# esp8266_rgb_controller_v2.net
KiCad netlist of a schematic drawn in EAGLE
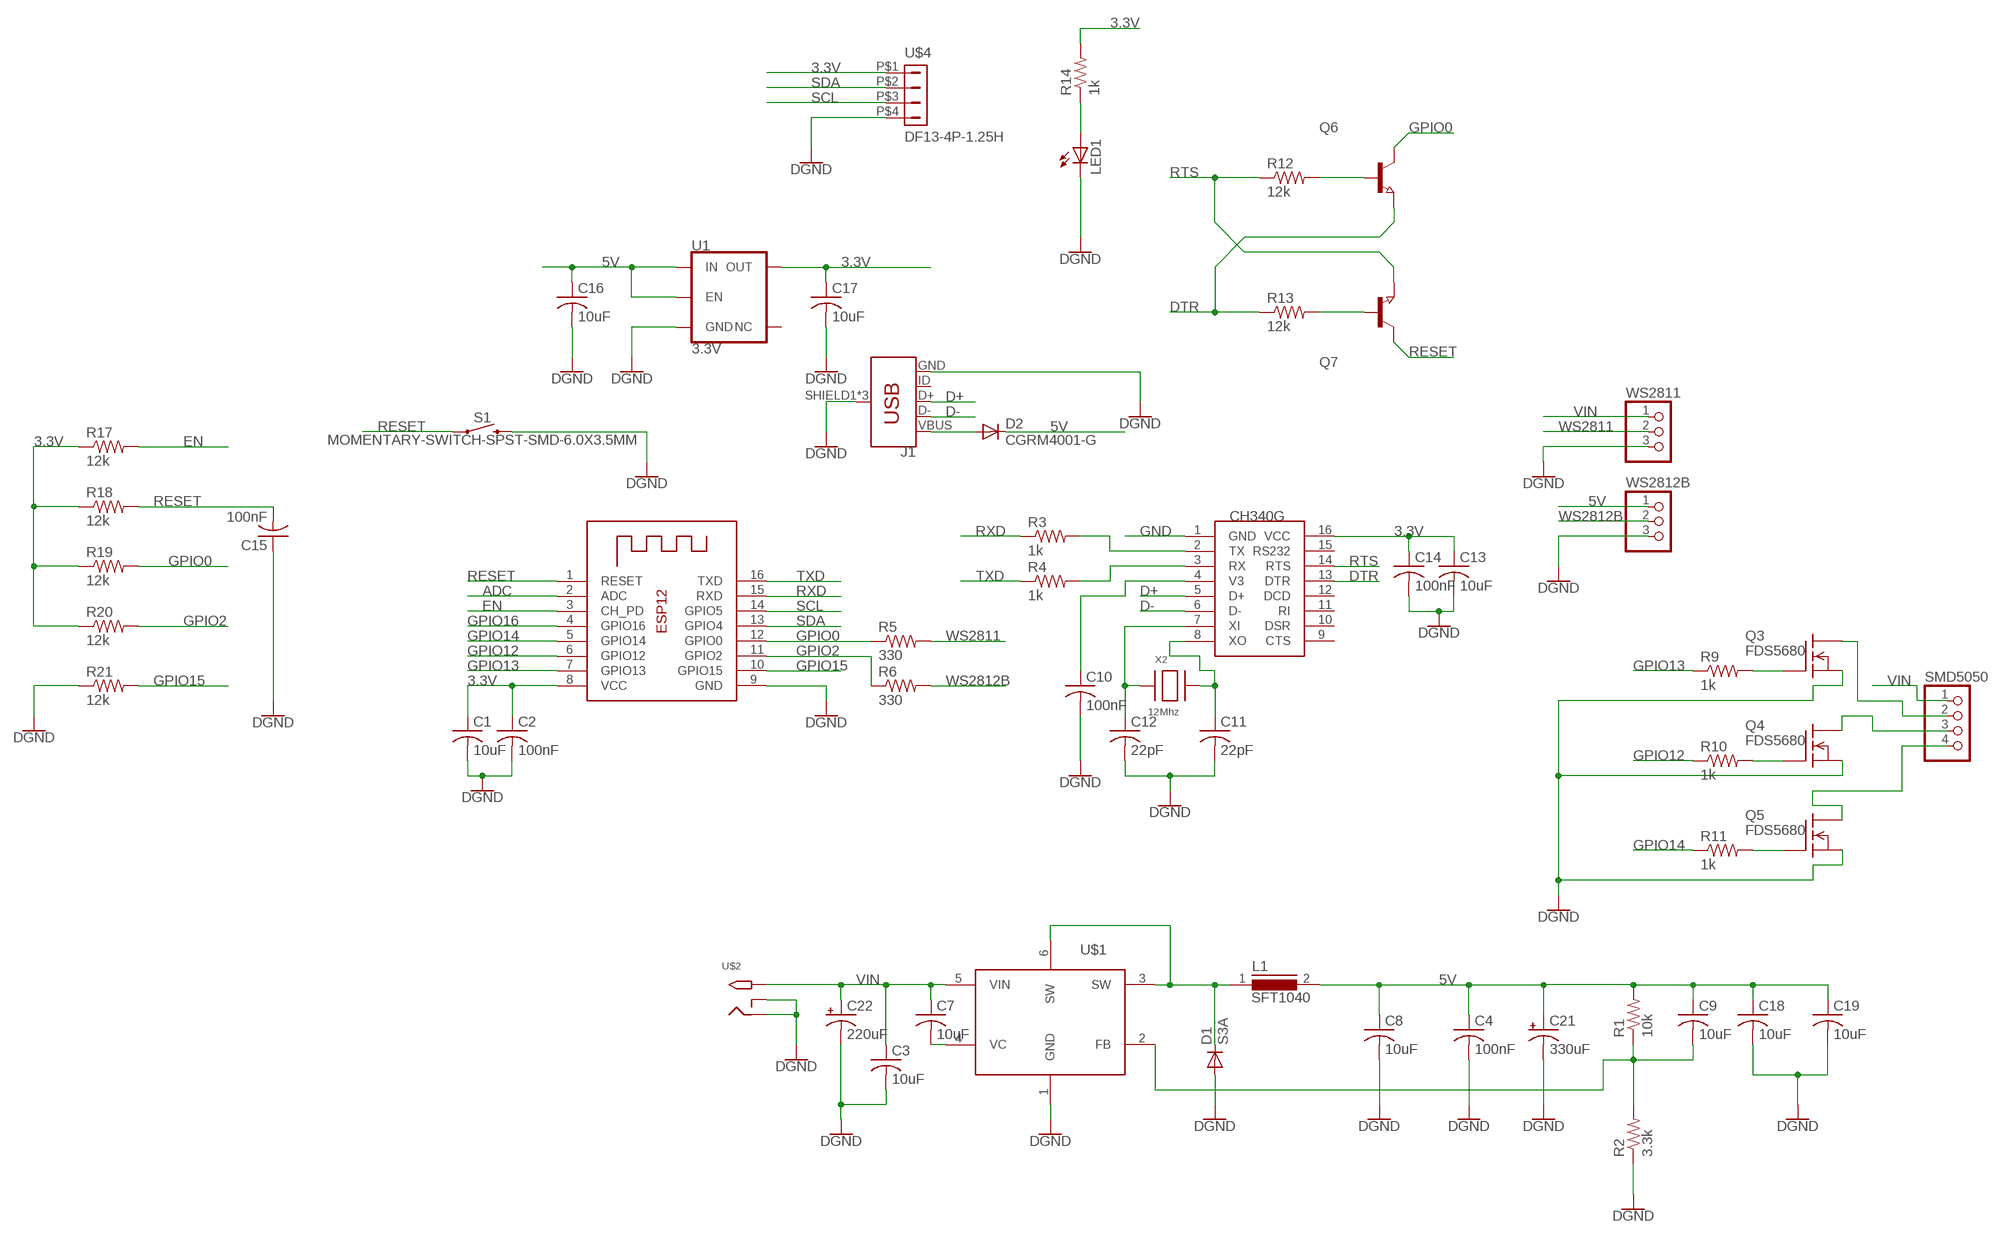
[diagram p0: schematic, sheet 1]

(export (version "E")
  (design (tool "Eeschema 10.0.6"))
  (components
    (comp (ref "C1")
      (value "10uF")
      (footprint "eagle-import:C0805")
      (libsource (lib "eagle-import") (part "C-USC0805"))
    )
    (comp (ref "C2")
      (value "100nF")
      (footprint "eagle-import:C0805")
      (libsource (lib "eagle-import") (part "C-USC0805"))
    )
    (comp (ref "C3")
      (value "10uF")
      (footprint "eagle-import:C0805")
      (libsource (lib "eagle-import") (part "C-USC0805"))
    )
    (comp (ref "C4")
      (value "100nF")
      (footprint "eagle-import:C0805")
      (libsource (lib "eagle-import") (part "C-USC0805"))
    )
    (comp (ref "C7")
      (value "10uF")
      (footprint "eagle-import:C0805")
      (libsource (lib "eagle-import") (part "C-USC0805"))
    )
    (comp (ref "C8")
      (value "10uF")
      (footprint "eagle-import:C0805")
      (libsource (lib "eagle-import") (part "C-USC0805"))
    )
    (comp (ref "C9")
      (value "10uF")
      (footprint "eagle-import:C0805")
      (libsource (lib "eagle-import") (part "C-USC0805"))
    )
    (comp (ref "C10")
      (value "100nF")
      (footprint "eagle-import:C0805")
      (libsource (lib "eagle-import") (part "C-USC0805"))
    )
    (comp (ref "C11")
      (value "22pF")
      (footprint "eagle-import:C0805")
      (libsource (lib "eagle-import") (part "C-USC0805"))
    )
    (comp (ref "C12")
      (value "22pF")
      (footprint "eagle-import:C0805")
      (libsource (lib "eagle-import") (part "C-USC0805"))
    )
    (comp (ref "C13")
      (value "10uF")
      (footprint "eagle-import:C0805")
      (libsource (lib "eagle-import") (part "C-USC0805"))
    )
    (comp (ref "C14")
      (value "100nF")
      (footprint "eagle-import:C0805")
      (libsource (lib "eagle-import") (part "C-USC0805"))
    )
    (comp (ref "C15")
      (value "100nF")
      (footprint "eagle-import:C0805")
      (libsource (lib "eagle-import") (part "C-USC0805"))
    )
    (comp (ref "C16")
      (value "10uF")
      (footprint "eagle-import:C1210")
      (libsource (lib "eagle-import") (part "C-USC1210"))
    )
    (comp (ref "C17")
      (value "10uF")
      (footprint "eagle-import:C0805")
      (libsource (lib "eagle-import") (part "C-USC0805"))
    )
    (comp (ref "C18")
      (value "10uF")
      (footprint "eagle-import:C0805")
      (libsource (lib "eagle-import") (part "C-USC0805"))
    )
    (comp (ref "C19")
      (value "10uF")
      (footprint "eagle-import:C0805")
      (libsource (lib "eagle-import") (part "C-USC0805"))
    )
    (comp (ref "C21")
      (value "330uF")
      (footprint "eagle-import:153CLV-0810")
      (libsource (lib "eagle-import") (part "CPOL-US153CLV-0810"))
    )
    (comp (ref "C22")
      (value "220uF")
      (footprint "eagle-import:153CLV-0810")
      (libsource (lib "eagle-import") (part "CPOL-US153CLV-0810"))
    )
    (comp (ref "D1")
      (value "S3A")
      (footprint "eagle-import:DO214AB")
      (fields (field (name "MF") "Fairchild"))
      (libsource (lib "eagle-import") (part "S3A"))
    )
    (comp (ref "D2")
      (value "CGRM4001-G")
      (footprint "eagle-import:SOD-123_MINI-SMA")
      (libsource (lib "eagle-import") (part "CGRM400-G1"))
    )
    (comp (ref "J1")
      (value "USB_MICRO-BREDUCED_PASTE")
      (footprint "eagle-import:USB-B-MICRO-SMD_RED_PASTE")
      (libsource (lib "eagle-import") (part "USB_MICRO-BREDUCED_PASTE"))
    )
    (comp (ref "L1")
      (value "SFT1040")
      (footprint "eagle-import:SFT1040")
      (libsource (lib "eagle-import") (part "SFT1040"))
    )
    (comp (ref "LED1")
      (value "LEDCHIP-LED0603")
      (footprint "eagle-import:CHIP-LED0603")
      (libsource (lib "eagle-import") (part "LEDCHIP-LED0603"))
    )
    (comp (ref "Q3")
      (value "FDS5680")
      (footprint "eagle-import:SO-8")
      (libsource (lib "eagle-import") (part "FDS5680"))
    )
    (comp (ref "Q4")
      (value "FDS5680")
      (footprint "eagle-import:SO-8")
      (libsource (lib "eagle-import") (part "FDS5680"))
    )
    (comp (ref "Q5")
      (value "FDS5680")
      (footprint "eagle-import:SO-8")
      (libsource (lib "eagle-import") (part "FDS5680"))
    )
    (comp (ref "Q6")
      (value "NPN-TRANSISTOR_SOT23")
      (footprint "eagle-import:SOT23")
      (libsource (lib "eagle-import") (part "NPN-TRANSISTOR_SOT23"))
    )
    (comp (ref "Q7")
      (value "NPN-TRANSISTOR_SOT23")
      (footprint "eagle-import:SOT23")
      (libsource (lib "eagle-import") (part "NPN-TRANSISTOR_SOT23"))
    )
    (comp (ref "R1")
      (value "10k")
      (footprint "eagle-import:R0805")
      (libsource (lib "eagle-import") (part "R-US_R0805"))
    )
    (comp (ref "R2")
      (value "3.3k")
      (footprint "eagle-import:R0805")
      (libsource (lib "eagle-import") (part "R-US_R0805"))
    )
    (comp (ref "R3")
      (value "1k")
      (footprint "eagle-import:R0805")
      (libsource (lib "eagle-import") (part "R-US_R0805"))
    )
    (comp (ref "R4")
      (value "1k")
      (footprint "eagle-import:R0805")
      (libsource (lib "eagle-import") (part "R-US_R0805"))
    )
    (comp (ref "R5")
      (value "330")
      (footprint "eagle-import:R0805")
      (libsource (lib "eagle-import") (part "R-US_R0805"))
    )
    (comp (ref "R6")
      (value "330")
      (footprint "eagle-import:R0805")
      (libsource (lib "eagle-import") (part "R-US_R0805"))
    )
    (comp (ref "R9")
      (value "1k")
      (footprint "eagle-import:R0805")
      (libsource (lib "eagle-import") (part "R-US_R0805"))
    )
    (comp (ref "R10")
      (value "1k")
      (footprint "eagle-import:R0805")
      (libsource (lib "eagle-import") (part "R-US_R0805"))
    )
    (comp (ref "R11")
      (value "1k")
      (footprint "eagle-import:R0805")
      (libsource (lib "eagle-import") (part "R-US_R0805"))
    )
    (comp (ref "R12")
      (value "12k")
      (footprint "eagle-import:R0805")
      (libsource (lib "eagle-import") (part "R-US_R0805"))
    )
    (comp (ref "R13")
      (value "12k")
      (footprint "eagle-import:R0805")
      (libsource (lib "eagle-import") (part "R-US_R0805"))
    )
    (comp (ref "R14")
      (value "1k")
      (footprint "eagle-import:R0805")
      (libsource (lib "eagle-import") (part "R-US_R0805"))
    )
    (comp (ref "R17")
      (value "12k")
      (footprint "eagle-import:R0805")
      (libsource (lib "eagle-import") (part "R-US_R0805"))
    )
    (comp (ref "R18")
      (value "12k")
      (footprint "eagle-import:R0805")
      (libsource (lib "eagle-import") (part "R-US_R0805"))
    )
    (comp (ref "R19")
      (value "12k")
      (footprint "eagle-import:R0805")
      (libsource (lib "eagle-import") (part "R-US_R0805"))
    )
    (comp (ref "R20")
      (value "12k")
      (footprint "eagle-import:R0805")
      (libsource (lib "eagle-import") (part "R-US_R0805"))
    )
    (comp (ref "R21")
      (value "12k")
      (footprint "eagle-import:R0805")
      (libsource (lib "eagle-import") (part "R-US_R0805"))
    )
    (comp (ref "S1")
      (value "MOMENTARY-SWITCH-SPST-SMD-6.0X3.5MM")
      (footprint "eagle-import:TACTILE_SWITCH_SMD_6.0X3.5MM")
      (libsource (lib "eagle-import") (part "MOMENTARY-SWITCH-SPST-SMD-6.0X3.5MM"))
    )
    (comp (ref "SMD5050")
      (value "PINHD-1X4")
      (footprint "eagle-import:1X04")
      (libsource (lib "eagle-import") (part "PINHD-1X4"))
    )
    (comp (ref "U$1")
      (value "XL4015")
      (footprint "eagle-import:TO263-5")
      (libsource (lib "eagle-import") (part "XL4015"))
    )
    (comp (ref "U$2")
      (value "2.1MMJACKTHM")
      (footprint "eagle-import:PJ-102A")
      (libsource (lib "eagle-import") (part "2.1MMJACKTHM"))
    )
    (comp (ref "U$3")
      (value "CH340G")
      (footprint "eagle-import:SOIC16")
      (libsource (lib "eagle-import") (part "CH340G"))
    )
    (comp (ref "U$4")
      (value "DF13-4P-1.25H")
      (footprint "eagle-import:DF13A-4P-1.25H")
      (libsource (lib "eagle-import") (part "DF13-4P-1.25H"))
    )
    (comp (ref "U1")
      (value "3.3V")
      (footprint "eagle-import:SOT23-5")
      (libsource (lib "eagle-import") (part "V_REG_AP2112K-3.3V"))
    )
    (comp (ref "WS2811")
      (value "PINHD-1X3")
      (footprint "eagle-import:1X03")
      (libsource (lib "eagle-import") (part "PINHD-1X3"))
    )
    (comp (ref "WS2812B")
      (value "PINHD-1X3")
      (footprint "eagle-import:1X03")
      (libsource (lib "eagle-import") (part "PINHD-1X3"))
    )
    (comp (ref "X1")
      (value "ESP-12F")
      (footprint "eagle-import:ESP-12")
      (libsource (lib "eagle-import") (part "ESP-12F"))
    )
    (comp (ref "X2")
      (value "12Mhz")
      (footprint "eagle-import:NX5032")
      (libsource (lib "eagle-import") (part "XTALNX5032"))
    )
  )
  (nets
    (net (code "1") (name "/3.3V") (class "Default")
      (node (ref "C1") (pin "1") (pinfunction "1_1") (pintype "passive"))
      (node (ref "C13") (pin "1") (pinfunction "1_1") (pintype "passive"))
      (node (ref "C14") (pin "1") (pinfunction "1_1") (pintype "passive"))
      (node (ref "C17") (pin "1") (pinfunction "1_1") (pintype "passive"))
      (node (ref "C2") (pin "1") (pinfunction "1_1") (pintype "passive"))
      (node (ref "R14") (pin "2") (pinfunction "2_2") (pintype "passive"))
      (node (ref "R17") (pin "1") (pinfunction "1_1") (pintype "passive"))
      (node (ref "R18") (pin "1") (pinfunction "1_1") (pintype "passive"))
      (node (ref "R19") (pin "1") (pinfunction "1_1") (pintype "passive"))
      (node (ref "R20") (pin "1") (pinfunction "1_1") (pintype "passive"))
      (node (ref "U$3") (pin "16") (pinfunction "VCC_16") (pintype "bidirectional"))
      (node (ref "U$4") (pin "P$1") (pinfunction "1_P$1") (pintype "passive"))
      (node (ref "U1") (pin "5") (pinfunction "OUT_5") (pintype "passive"))
      (node (ref "X1") (pin "8") (pinfunction "VCC_8") (pintype "power_in"))
    )
    (net (code "2") (name "/5V") (class "Default")
      (node (ref "C16") (pin "1") (pinfunction "1_1") (pintype "passive"))
      (node (ref "C18") (pin "1") (pinfunction "1_1") (pintype "passive"))
      (node (ref "C19") (pin "1") (pinfunction "1_1") (pintype "passive"))
      (node (ref "C21") (pin "+") (pinfunction "+_+") (pintype "passive"))
      (node (ref "C4") (pin "1") (pinfunction "1_1") (pintype "passive"))
      (node (ref "C8") (pin "1") (pinfunction "1_1") (pintype "passive"))
      (node (ref "C9") (pin "1") (pinfunction "1_1") (pintype "passive"))
      (node (ref "D2") (pin "C") (pinfunction "C_C") (pintype "passive"))
      (node (ref "L1") (pin "2") (pinfunction "2_2") (pintype "passive"))
      (node (ref "R1") (pin "2") (pinfunction "2_2") (pintype "passive"))
      (node (ref "U1") (pin "1") (pinfunction "IN_1") (pintype "input"))
      (node (ref "U1") (pin "3") (pinfunction "EN_3") (pintype "input"))
      (node (ref "WS2812B") (pin "1") (pinfunction "1_1") (pintype "passive"))
    )
    (net (code "3") (name "/ADC") (class "Default")
      (node (ref "X1") (pin "2") (pinfunction "ADC_2") (pintype "passive"))
    )
    (net (code "4") (name "/D+") (class "Default")
      (node (ref "J1") (pin "D+") (pinfunction "D+_D+") (pintype "bidirectional"))
      (node (ref "U$3") (pin "5") (pinfunction "D+_5") (pintype "bidirectional"))
    )
    (net (code "5") (name "/D-") (class "Default")
      (node (ref "J1") (pin "D-") (pinfunction "D-_D-") (pintype "bidirectional"))
      (node (ref "U$3") (pin "6") (pinfunction "D-_6") (pintype "bidirectional"))
    )
    (net (code "6") (name "/DTR") (class "Default")
      (node (ref "Q6") (pin "2") (pinfunction "E_2") (pintype "passive"))
      (node (ref "R13") (pin "1") (pinfunction "1_1") (pintype "passive"))
      (node (ref "U$3") (pin "13") (pinfunction "DTR_13") (pintype "bidirectional"))
    )
    (net (code "7") (name "/EN") (class "Default")
      (node (ref "R17") (pin "2") (pinfunction "2_2") (pintype "passive"))
      (node (ref "X1") (pin "3") (pinfunction "CH_PD_3") (pintype "input"))
    )
    (net (code "8") (name "/GPIO0") (class "Default")
      (node (ref "Q6") (pin "3") (pinfunction "C_3") (pintype "passive"))
      (node (ref "R19") (pin "2") (pinfunction "2_2") (pintype "passive"))
      (node (ref "R5") (pin "1") (pinfunction "1_1") (pintype "passive"))
      (node (ref "X1") (pin "12") (pinfunction "GPIO0_12") (pintype "bidirectional"))
    )
    (net (code "9") (name "/GPIO2") (class "Default")
      (node (ref "R20") (pin "2") (pinfunction "2_2") (pintype "passive"))
      (node (ref "R6") (pin "1") (pinfunction "1_1") (pintype "passive"))
      (node (ref "X1") (pin "11") (pinfunction "GPIO2_11") (pintype "bidirectional"))
    )
    (net (code "10") (name "/GPIO12") (class "Default")
      (node (ref "R10") (pin "1") (pinfunction "1_1") (pintype "passive"))
      (node (ref "X1") (pin "6") (pinfunction "GPIO12_6") (pintype "bidirectional"))
    )
    (net (code "11") (name "/GPIO13") (class "Default")
      (node (ref "R9") (pin "1") (pinfunction "1_1") (pintype "passive"))
      (node (ref "X1") (pin "7") (pinfunction "GPIO13_7") (pintype "bidirectional"))
    )
    (net (code "12") (name "/GPIO14") (class "Default")
      (node (ref "R11") (pin "1") (pinfunction "1_1") (pintype "passive"))
      (node (ref "X1") (pin "5") (pinfunction "GPIO14_5") (pintype "bidirectional"))
    )
    (net (code "13") (name "/GPIO15") (class "Default")
      (node (ref "R21") (pin "2") (pinfunction "2_2") (pintype "passive"))
      (node (ref "X1") (pin "10") (pinfunction "GPIO15_10") (pintype "bidirectional"))
    )
    (net (code "14") (name "/GPIO16") (class "Default")
      (node (ref "X1") (pin "4") (pinfunction "GPIO16_4") (pintype "bidirectional"))
    )
    (net (code "15") (name "/RESET") (class "Default")
      (node (ref "C15") (pin "2") (pinfunction "2_2") (pintype "passive"))
      (node (ref "Q7") (pin "3") (pinfunction "C_3") (pintype "passive"))
      (node (ref "R18") (pin "2") (pinfunction "2_2") (pintype "passive"))
      (node (ref "S1") (pin "1") (pinfunction "1_1") (pintype "passive"))
      (node (ref "X1") (pin "1") (pinfunction "RESET_1") (pintype "input"))
    )
    (net (code "16") (name "/RTS") (class "Default")
      (node (ref "Q7") (pin "2") (pinfunction "E_2") (pintype "passive"))
      (node (ref "R12") (pin "1") (pinfunction "1_1") (pintype "passive"))
      (node (ref "U$3") (pin "14") (pinfunction "RTS_14") (pintype "bidirectional"))
    )
    (net (code "17") (name "/RXD") (class "Default")
      (node (ref "R3") (pin "1") (pinfunction "1_1") (pintype "passive"))
      (node (ref "X1") (pin "15") (pinfunction "RXD_15") (pintype "input"))
    )
    (net (code "18") (name "/SCL") (class "Default")
      (node (ref "U$4") (pin "P$3") (pinfunction "3_P$3") (pintype "passive"))
      (node (ref "X1") (pin "14") (pinfunction "GPIO5_14") (pintype "bidirectional"))
    )
    (net (code "19") (name "/SDA") (class "Default")
      (node (ref "U$4") (pin "P$2") (pinfunction "2_P$2") (pintype "passive"))
      (node (ref "X1") (pin "13") (pinfunction "GPIO4_13") (pintype "bidirectional"))
    )
    (net (code "20") (name "/TXD") (class "Default")
      (node (ref "R4") (pin "1") (pinfunction "1_1") (pintype "passive"))
      (node (ref "X1") (pin "16") (pinfunction "TXD_16") (pintype "output"))
    )
    (net (code "21") (name "/VIN") (class "Default")
      (node (ref "C22") (pin "+") (pinfunction "+_+") (pintype "passive"))
      (node (ref "C3") (pin "1") (pinfunction "1_1") (pintype "passive"))
      (node (ref "C7") (pin "1") (pinfunction "1_1") (pintype "passive"))
      (node (ref "SMD5050") (pin "1") (pinfunction "1_1") (pintype "passive"))
      (node (ref "U$1") (pin "5") (pinfunction "VIN_5") (pintype "bidirectional"))
      (node (ref "U$2") (pin "TIP") (pinfunction "TIP_TIP") (pintype "bidirectional"))
      (node (ref "WS2811") (pin "1") (pinfunction "1_1") (pintype "passive"))
    )
    (net (code "22") (name "/WS2811") (class "Default")
      (node (ref "R5") (pin "2") (pinfunction "2_2") (pintype "passive"))
      (node (ref "WS2811") (pin "2") (pinfunction "2_2") (pintype "passive"))
    )
    (net (code "23") (name "/WS2812B") (class "Default")
      (node (ref "R6") (pin "2") (pinfunction "2_2") (pintype "passive"))
      (node (ref "WS2812B") (pin "2") (pinfunction "2_2") (pintype "passive"))
    )
    (net (code "24") (name "DGND") (class "Default")
      (node (ref "C1") (pin "2") (pinfunction "2_2") (pintype "passive"))
      (node (ref "C10") (pin "2") (pinfunction "2_2") (pintype "passive"))
      (node (ref "C11") (pin "2") (pinfunction "2_2") (pintype "passive"))
      (node (ref "C12") (pin "2") (pinfunction "2_2") (pintype "passive"))
      (node (ref "C13") (pin "2") (pinfunction "2_2") (pintype "passive"))
      (node (ref "C14") (pin "2") (pinfunction "2_2") (pintype "passive"))
      (node (ref "C15") (pin "1") (pinfunction "1_1") (pintype "passive"))
      (node (ref "C16") (pin "2") (pinfunction "2_2") (pintype "passive"))
      (node (ref "C17") (pin "2") (pinfunction "2_2") (pintype "passive"))
      (node (ref "C18") (pin "2") (pinfunction "2_2") (pintype "passive"))
      (node (ref "C19") (pin "2") (pinfunction "2_2") (pintype "passive"))
      (node (ref "C2") (pin "2") (pinfunction "2_2") (pintype "passive"))
      (node (ref "C21") (pin "-") (pinfunction "-_-") (pintype "passive"))
      (node (ref "C22") (pin "-") (pinfunction "-_-") (pintype "passive"))
      (node (ref "C3") (pin "2") (pinfunction "2_2") (pintype "passive"))
      (node (ref "C4") (pin "2") (pinfunction "2_2") (pintype "passive"))
      (node (ref "C8") (pin "2") (pinfunction "2_2") (pintype "passive"))
      (node (ref "D1") (pin "A") (pinfunction "A_A") (pintype "passive"))
      (node (ref "J1") (pin "GND") (pinfunction "GND_GND") (pintype "power_in"))
      (node (ref "J1") (pin "SHIELD1") (pinfunction "SHIELD_SHIELD1") (pintype "bidirectional"))
      (node (ref "J1") (pin "SHIELD2") (pinfunction "SHIELD_SHIELD2") (pintype "bidirectional"))
      (node (ref "J1") (pin "SHIELD3") (pinfunction "SHIELD_SHIELD3") (pintype "bidirectional"))
      (node (ref "LED1") (pin "C") (pinfunction "C_C") (pintype "passive"))
      (node (ref "Q3") (pin "1") (pinfunction "S_1") (pintype "passive"))
      (node (ref "Q3") (pin "2") (pinfunction "S_2") (pintype "passive"))
      (node (ref "Q3") (pin "3") (pinfunction "S_3") (pintype "passive"))
      (node (ref "Q4") (pin "1") (pinfunction "S_1") (pintype "passive"))
      (node (ref "Q4") (pin "2") (pinfunction "S_2") (pintype "passive"))
      (node (ref "Q4") (pin "3") (pinfunction "S_3") (pintype "passive"))
      (node (ref "Q5") (pin "1") (pinfunction "S_1") (pintype "passive"))
      (node (ref "Q5") (pin "2") (pinfunction "S_2") (pintype "passive"))
      (node (ref "Q5") (pin "3") (pinfunction "S_3") (pintype "passive"))
      (node (ref "R2") (pin "1") (pinfunction "1_1") (pintype "passive"))
      (node (ref "R21") (pin "1") (pinfunction "1_1") (pintype "passive"))
      (node (ref "S1") (pin "2") (pinfunction "2_2") (pintype "passive"))
      (node (ref "U$1") (pin "1") (pinfunction "GND_1") (pintype "bidirectional"))
      (node (ref "U$2") (pin "RING") (pinfunction "RING_RING") (pintype "bidirectional"))
      (node (ref "U$2") (pin "RING_SW") (pinfunction "RING_SW_RING_SW") (pintype "bidirectional"))
      (node (ref "U$3") (pin "1") (pinfunction "GND_1") (pintype "bidirectional"))
      (node (ref "U$4") (pin "P$4") (pinfunction "4_P$4") (pintype "passive"))
      (node (ref "U1") (pin "2") (pinfunction "GND_2") (pintype "input"))
      (node (ref "WS2811") (pin "3") (pinfunction "3_3") (pintype "passive"))
      (node (ref "WS2812B") (pin "3") (pinfunction "3_3") (pintype "passive"))
      (node (ref "X1") (pin "9") (pinfunction "GND_9") (pintype "power_in"))
    )
    (net (code "25") (name "Net-(D1-PadC)") (class "Default")
      (node (ref "D1") (pin "C") (pinfunction "C_C") (pintype "passive"))
      (node (ref "L1") (pin "1") (pinfunction "1_1") (pintype "passive"))
      (node (ref "U$1") (pin "3") (pinfunction "SW_3") (pintype "bidirectional"))
      (node (ref "U$1") (pin "6") (pinfunction "SW_6") (pintype "bidirectional"))
    )
    (net (code "26") (name "Net-(D2-PadA)") (class "Default")
      (node (ref "D2") (pin "A") (pinfunction "A_A") (pintype "passive"))
      (node (ref "J1") (pin "VBUS") (pinfunction "VBUS_VBUS") (pintype "power_in"))
    )
    (net (code "27") (name "Net-(LED1-PadA)") (class "Default")
      (node (ref "LED1") (pin "A") (pinfunction "A_A") (pintype "passive"))
      (node (ref "R14") (pin "1") (pinfunction "1_1") (pintype "passive"))
    )
    (net (code "28") (name "Net-(Q3-D-Pad5)") (class "Default")
      (node (ref "Q3") (pin "5") (pinfunction "D_5") (pintype "passive"))
      (node (ref "Q3") (pin "6") (pinfunction "D_6") (pintype "passive"))
      (node (ref "Q3") (pin "7") (pinfunction "D_7") (pintype "passive"))
      (node (ref "Q3") (pin "8") (pinfunction "D_8") (pintype "passive"))
      (node (ref "SMD5050") (pin "2") (pinfunction "2_2") (pintype "passive"))
    )
    (net (code "29") (name "Net-(Q3-G)") (class "Default")
      (node (ref "Q3") (pin "4") (pinfunction "G_4") (pintype "passive"))
      (node (ref "R9") (pin "2") (pinfunction "2_2") (pintype "passive"))
    )
    (net (code "30") (name "Net-(Q4-D-Pad5)") (class "Default")
      (node (ref "Q4") (pin "5") (pinfunction "D_5") (pintype "passive"))
      (node (ref "Q4") (pin "6") (pinfunction "D_6") (pintype "passive"))
      (node (ref "Q4") (pin "7") (pinfunction "D_7") (pintype "passive"))
      (node (ref "Q4") (pin "8") (pinfunction "D_8") (pintype "passive"))
      (node (ref "SMD5050") (pin "3") (pinfunction "3_3") (pintype "passive"))
    )
    (net (code "31") (name "Net-(Q4-G)") (class "Default")
      (node (ref "Q4") (pin "4") (pinfunction "G_4") (pintype "passive"))
      (node (ref "R10") (pin "2") (pinfunction "2_2") (pintype "passive"))
    )
    (net (code "32") (name "Net-(Q5-D-Pad5)") (class "Default")
      (node (ref "Q5") (pin "5") (pinfunction "D_5") (pintype "passive"))
      (node (ref "Q5") (pin "6") (pinfunction "D_6") (pintype "passive"))
      (node (ref "Q5") (pin "7") (pinfunction "D_7") (pintype "passive"))
      (node (ref "Q5") (pin "8") (pinfunction "D_8") (pintype "passive"))
      (node (ref "SMD5050") (pin "4") (pinfunction "4_4") (pintype "passive"))
    )
    (net (code "33") (name "Net-(Q5-G)") (class "Default")
      (node (ref "Q5") (pin "4") (pinfunction "G_4") (pintype "passive"))
      (node (ref "R11") (pin "2") (pinfunction "2_2") (pintype "passive"))
    )
    (net (code "34") (name "Net-(Q6-B)") (class "Default")
      (node (ref "Q6") (pin "1") (pinfunction "B_1") (pintype "passive"))
      (node (ref "R12") (pin "2") (pinfunction "2_2") (pintype "passive"))
    )
    (net (code "35") (name "Net-(Q7-B)") (class "Default")
      (node (ref "Q7") (pin "1") (pinfunction "B_1") (pintype "passive"))
      (node (ref "R13") (pin "2") (pinfunction "2_2") (pintype "passive"))
    )
    (net (code "36") (name "Net-(U$1-FB)") (class "Default")
      (node (ref "C9") (pin "2") (pinfunction "2_2") (pintype "passive"))
      (node (ref "R1") (pin "1") (pinfunction "1_1") (pintype "passive"))
      (node (ref "R2") (pin "2") (pinfunction "2_2") (pintype "passive"))
      (node (ref "U$1") (pin "2") (pinfunction "FB_2") (pintype "bidirectional"))
    )
    (net (code "37") (name "Net-(U$1-VC)") (class "Default")
      (node (ref "C7") (pin "2") (pinfunction "2_2") (pintype "passive"))
      (node (ref "U$1") (pin "4") (pinfunction "VC_4") (pintype "bidirectional"))
    )
    (net (code "38") (name "Net-(U$3-RX)") (class "Default")
      (node (ref "R4") (pin "2") (pinfunction "2_2") (pintype "passive"))
      (node (ref "U$3") (pin "3") (pinfunction "RX_3") (pintype "bidirectional"))
    )
    (net (code "39") (name "Net-(U$3-TX)") (class "Default")
      (node (ref "R3") (pin "2") (pinfunction "2_2") (pintype "passive"))
      (node (ref "U$3") (pin "2") (pinfunction "TX_2") (pintype "bidirectional"))
    )
    (net (code "40") (name "Net-(U$3-V3)") (class "Default")
      (node (ref "C10") (pin "1") (pinfunction "1_1") (pintype "passive"))
      (node (ref "U$3") (pin "4") (pinfunction "V3_4") (pintype "bidirectional"))
    )
    (net (code "41") (name "Net-(U$3-XI)") (class "Default")
      (node (ref "C12") (pin "1") (pinfunction "1_1") (pintype "passive"))
      (node (ref "U$3") (pin "7") (pinfunction "XI_7") (pintype "bidirectional"))
      (node (ref "X2") (pin "P$1") (pinfunction "P$1_P$1") (pintype "bidirectional"))
    )
    (net (code "42") (name "Net-(U$3-XO)") (class "Default")
      (node (ref "C11") (pin "1") (pinfunction "1_1") (pintype "passive"))
      (node (ref "U$3") (pin "8") (pinfunction "XO_8") (pintype "bidirectional"))
      (node (ref "X2") (pin "P$2") (pinfunction "P$2_P$2") (pintype "bidirectional"))
    )
    (net (code "43") (name "unconnected-(J1-PadID)") (class "Default")
      (node (ref "J1") (pin "ID") (pinfunction "ID_ID") (pintype "bidirectional"))
    )
    (net (code "44") (name "unconnected-(U$3-CTS-Pad9)") (class "Default")
      (node (ref "U$3") (pin "9") (pinfunction "CTS_9") (pintype "bidirectional"))
    )
    (net (code "45") (name "unconnected-(U$3-DCD-Pad12)") (class "Default")
      (node (ref "U$3") (pin "12") (pinfunction "DCD_12") (pintype "bidirectional"))
    )
    (net (code "46") (name "unconnected-(U$3-DSR-Pad10)") (class "Default")
      (node (ref "U$3") (pin "10") (pinfunction "DSR_10") (pintype "bidirectional"))
    )
    (net (code "47") (name "unconnected-(U$3-RI-Pad11)") (class "Default")
      (node (ref "U$3") (pin "11") (pinfunction "RI_11") (pintype "bidirectional"))
    )
    (net (code "48") (name "unconnected-(U$3-RS232-Pad15)") (class "Default")
      (node (ref "U$3") (pin "15") (pinfunction "RS232_15") (pintype "bidirectional"))
    )
    (net (code "49") (name "unconnected-(U1-NC-Pad4)") (class "Default")
      (node (ref "U1") (pin "4") (pinfunction "NC_4") (pintype "no_connect"))
    )
  )
)
